# SoundChip.net
KiCad netlist of a schematic drawn in Altium Designer
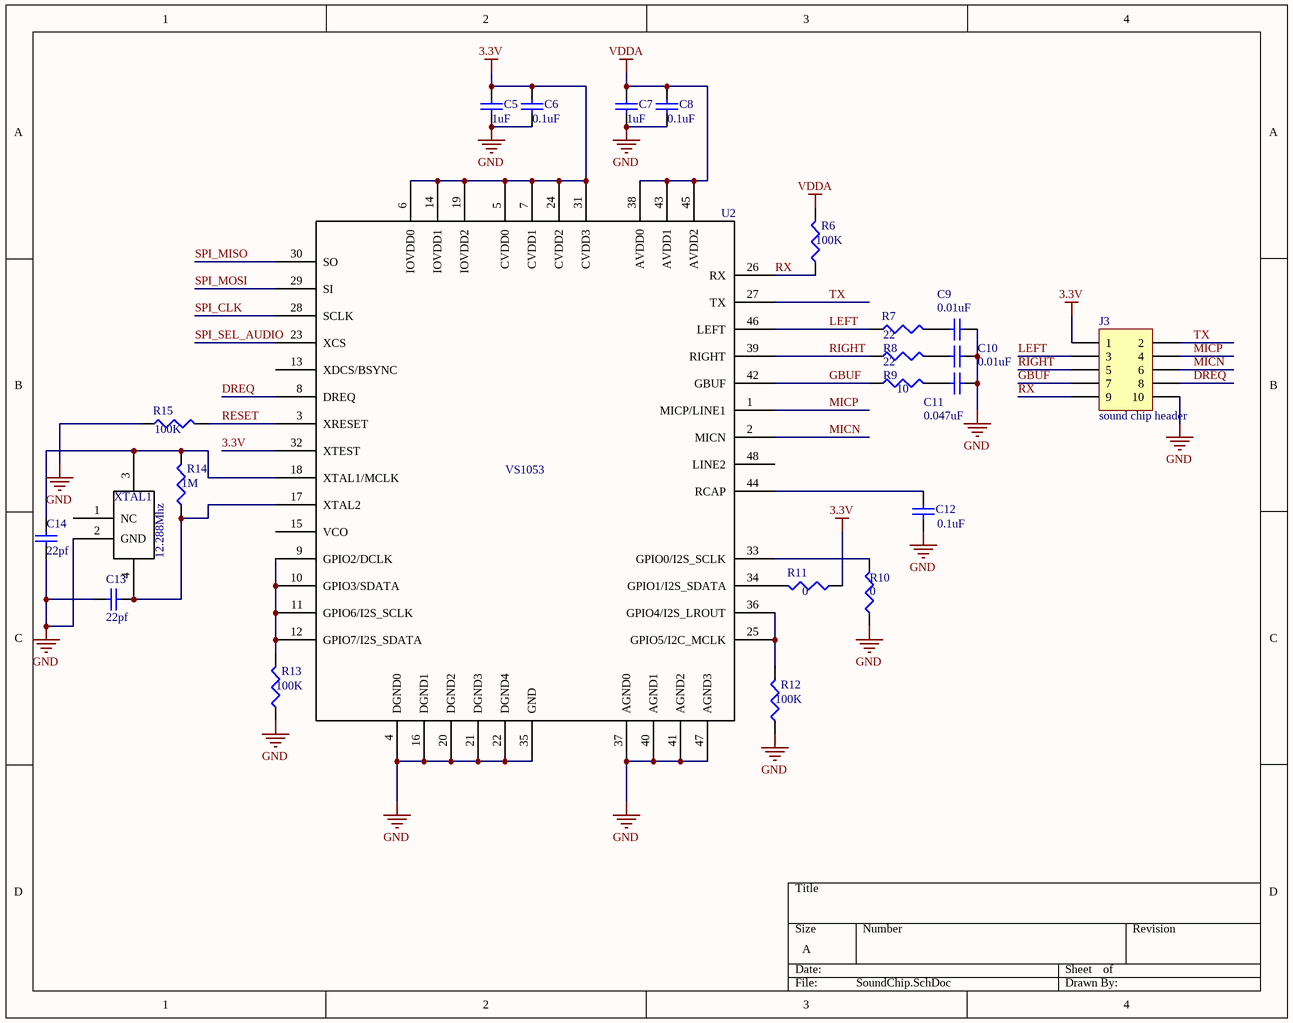
[diagram p0: SoundChip.SchDoc]

(export (version "E")
  (design (tool "Eeschema 10.0.6"))
  (components
    (comp (ref "C5")
      (value "1uF")
      (footprint "CAPC1608L")
      (description "Capacitor (Semiconductor SIM Model)")
      (fields (field (name "Comment") "Cap Semi") (field (name "PUBLISHER") "Altium Limited"))
      (libsource (lib "Miscellaneous Devices") (part "Cap Semi"))
    )
    (comp (ref "C6")
      (value "0.1uF")
      (footprint "CAPC1005L")
      (description "Capacitor (Semiconductor SIM Model)")
      (fields (field (name "Comment") "Cap Semi") (field (name "PUBLISHER") "Altium Limited"))
      (libsource (lib "Miscellaneous Devices") (part "Cap Semi"))
    )
    (comp (ref "C7")
      (value "1uF")
      (footprint "CAPC1608L")
      (description "Capacitor (Semiconductor SIM Model)")
      (fields (field (name "Comment") "Cap Semi") (field (name "PUBLISHER") "Altium Limited"))
      (libsource (lib "Miscellaneous Devices") (part "Cap Semi"))
    )
    (comp (ref "C8")
      (value "0.1uF")
      (footprint "CAPC1005L")
      (description "Capacitor (Semiconductor SIM Model)")
      (fields (field (name "Comment") "Cap Semi") (field (name "PUBLISHER") "Altium Limited"))
      (libsource (lib "Miscellaneous Devices") (part "Cap Semi"))
    )
    (comp (ref "C9")
      (value "0.01uF")
      (footprint "CAPC1005L")
      (description "Capacitor (Semiconductor SIM Model)")
      (fields (field (name "Comment") "Cap Semi") (field (name "PUBLISHER") "Altium Limited"))
      (libsource (lib "Miscellaneous Devices") (part "Cap Semi"))
    )
    (comp (ref "C10")
      (value "0.01uF")
      (footprint "CAPC1005L")
      (description "Capacitor (Semiconductor SIM Model)")
      (fields (field (name "Comment") "Cap Semi") (field (name "PUBLISHER") "Altium Limited"))
      (libsource (lib "Miscellaneous Devices") (part "Cap Semi"))
    )
    (comp (ref "C11")
      (value "0.047uF")
      (footprint "CAPC1005L")
      (description "Capacitor (Semiconductor SIM Model)")
      (fields (field (name "Comment") "Cap Semi") (field (name "PUBLISHER") "Altium Limited"))
      (libsource (lib "Miscellaneous Devices") (part "Cap Semi"))
    )
    (comp (ref "C12")
      (value "0.1uF")
      (footprint "CAPC3216L")
      (description "Capacitor (Semiconductor SIM Model)")
      (fields (field (name "Comment") "Cap Semi") (field (name "PUBLISHER") "Altium Limited"))
      (libsource (lib "Miscellaneous Devices") (part "Cap Semi"))
    )
    (comp (ref "C13")
      (value "22pf")
      (footprint "CAPC1005L")
      (description "Capacitor (Semiconductor SIM Model)")
      (fields (field (name "Comment") "Cap Semi") (field (name "PUBLISHER") "Altium Limited"))
      (libsource (lib "Miscellaneous Devices") (part "Cap Semi"))
    )
    (comp (ref "C14")
      (value "22pf")
      (footprint "CAPC1005L")
      (description "Capacitor (Semiconductor SIM Model)")
      (fields (field (name "Comment") "Cap Semi") (field (name "PUBLISHER") "Altium Limited"))
      (libsource (lib "Miscellaneous Devices") (part "Cap Semi"))
    )
    (comp (ref "J3")
      (value "sound chip header")
      (footprint "HDR2X5")
      (description "Header, 5-Pin, Dual row")
      (fields (field (name "PUBLISHER") "Altium Limited"))
      (libsource (lib "Miscellaneous Connectors") (part "Header 5X2"))
    )
    (comp (ref "R6")
      (value "100K")
      (footprint "RESC1608L")
      (description "Resistor")
      (fields (field (name "Comment") "Res3") (field (name "PUBLISHER") "Altium Limited"))
      (libsource (lib "Miscellaneous Devices") (part "Res3"))
    )
    (comp (ref "R7")
      (value "22")
      (footprint "RESC1608L")
      (description "Resistor")
      (fields (field (name "Comment") "Res3") (field (name "PUBLISHER") "Altium Limited"))
      (libsource (lib "Miscellaneous Devices") (part "Res3"))
    )
    (comp (ref "R8")
      (value "22")
      (footprint "RESC1608L")
      (description "Resistor")
      (fields (field (name "Comment") "Res3") (field (name "PUBLISHER") "Altium Limited"))
      (libsource (lib "Miscellaneous Devices") (part "Res3"))
    )
    (comp (ref "R9")
      (value "10")
      (footprint "RESC1608L")
      (description "Resistor")
      (fields (field (name "Comment") "Res3") (field (name "PUBLISHER") "Altium Limited"))
      (libsource (lib "Miscellaneous Devices") (part "Res3"))
    )
    (comp (ref "R10")
      (value "0")
      (footprint "RESC1608L")
      (description "Resistor")
      (fields (field (name "Comment") "Res3") (field (name "PUBLISHER") "Altium Limited"))
      (libsource (lib "Miscellaneous Devices") (part "Res3"))
    )
    (comp (ref "R11")
      (value "0")
      (footprint "RESC1608L")
      (description "Resistor")
      (fields (field (name "Comment") "Res3") (field (name "PUBLISHER") "Altium Limited"))
      (libsource (lib "Miscellaneous Devices") (part "Res3"))
    )
    (comp (ref "R12")
      (value "100K")
      (footprint "RESC1608L")
      (description "Resistor")
      (fields (field (name "Comment") "Res3") (field (name "PUBLISHER") "Altium Limited"))
      (libsource (lib "Miscellaneous Devices") (part "Res3"))
    )
    (comp (ref "R13")
      (value "100K")
      (footprint "RESC1608L")
      (description "Resistor")
      (fields (field (name "Comment") "Res3") (field (name "PUBLISHER") "Altium Limited"))
      (libsource (lib "Miscellaneous Devices") (part "Res3"))
    )
    (comp (ref "R14")
      (value "1M")
      (footprint "RESC1608L")
      (description "Resistor")
      (fields (field (name "Comment") "Res3") (field (name "PUBLISHER") "Altium Limited"))
      (libsource (lib "Miscellaneous Devices") (part "Res3"))
    )
    (comp (ref "R15")
      (value "100K")
      (footprint "RESC1608L")
      (description "Resistor")
      (fields (field (name "Comment") "Res3") (field (name "PUBLISHER") "Altium Limited"))
      (libsource (lib "Miscellaneous Devices") (part "Res3"))
    )
    (comp (ref "U2") (value "VS1053") (footprint "LQFP-48") (libsource (lib "mrone") (part "VS1053")))
    (comp (ref "XTAL1")
      (value "12.288Mhz")
      (footprint "Crystal")
      (description "FOX924B crystal")
      (libsource (lib "mrone") (part "SoundCrystal"))
    )
  )
  (nets
    (net (code "1") (name "/DREQ") (class "Default")
      (node (ref "J3") (pin "8") (pinfunction "8_8") (pintype "passive"))
      (node (ref "U2") (pin "8") (pinfunction "DREQ_8") (pintype "passive"))
    )
    (net (code "2") (name "/GBUF") (class "Default")
      (node (ref "J3") (pin "7") (pinfunction "7_7") (pintype "passive"))
      (node (ref "R9") (pin "1") (pinfunction "1_1") (pintype "passive"))
      (node (ref "U2") (pin "42") (pinfunction "GBUF_42") (pintype "passive"))
    )
    (net (code "3") (name "/LEFT") (class "Default")
      (node (ref "J3") (pin "3") (pinfunction "3_3") (pintype "passive"))
      (node (ref "R7") (pin "1") (pinfunction "1_1") (pintype "passive"))
      (node (ref "U2") (pin "46") (pinfunction "LEFT_46") (pintype "passive"))
    )
    (net (code "4") (name "/MICN") (class "Default")
      (node (ref "J3") (pin "6") (pinfunction "6_6") (pintype "passive"))
      (node (ref "U2") (pin "2") (pinfunction "MICN_2") (pintype "passive"))
    )
    (net (code "5") (name "/MICP") (class "Default")
      (node (ref "J3") (pin "4") (pinfunction "4_4") (pintype "passive"))
      (node (ref "U2") (pin "1") (pinfunction "MICP/LINE1_1") (pintype "passive"))
    )
    (net (code "6") (name "/RESET") (class "Default")
      (node (ref "R15") (pin "2") (pinfunction "2_2") (pintype "passive"))
      (node (ref "U2") (pin "3") (pinfunction "XRESET_3") (pintype "passive"))
    )
    (net (code "7") (name "/RIGHT") (class "Default")
      (node (ref "J3") (pin "5") (pinfunction "5_5") (pintype "passive"))
      (node (ref "R8") (pin "1") (pinfunction "1_1") (pintype "passive"))
      (node (ref "U2") (pin "39") (pinfunction "RIGHT_39") (pintype "passive"))
    )
    (net (code "8") (name "/RX") (class "Default")
      (node (ref "J3") (pin "9") (pinfunction "9_9") (pintype "passive"))
      (node (ref "R6") (pin "1") (pinfunction "1_1") (pintype "passive"))
      (node (ref "U2") (pin "26") (pinfunction "RX_26") (pintype "passive"))
    )
    (net (code "9") (name "/SPI_CLK") (class "Default")
      (node (ref "U2") (pin "28") (pinfunction "SCLK_28") (pintype "passive"))
    )
    (net (code "10") (name "/SPI_MISO") (class "Default")
      (node (ref "U2") (pin "30") (pinfunction "SO_30") (pintype "passive"))
    )
    (net (code "11") (name "/SPI_MOSI") (class "Default")
      (node (ref "U2") (pin "29") (pinfunction "SI_29") (pintype "passive"))
    )
    (net (code "12") (name "/SPI_SEL_AUDIO") (class "Default")
      (node (ref "U2") (pin "23") (pinfunction "XCS_23") (pintype "passive"))
    )
    (net (code "13") (name "/TX") (class "Default")
      (node (ref "J3") (pin "2") (pinfunction "2_2") (pintype "passive"))
      (node (ref "U2") (pin "27") (pinfunction "TX_27") (pintype "passive"))
    )
    (net (code "14") (name "3.3V") (class "Default")
      (node (ref "C5") (pin "1") (pinfunction "1_1") (pintype "passive"))
      (node (ref "C6") (pin "2") (pinfunction "2_2") (pintype "passive"))
      (node (ref "J3") (pin "1") (pinfunction "1_1") (pintype "passive"))
      (node (ref "R11") (pin "1") (pinfunction "1_1") (pintype "passive"))
      (node (ref "U2") (pin "14") (pinfunction "IOVDD1_14") (pintype "passive"))
      (node (ref "U2") (pin "19") (pinfunction "IOVDD2_19") (pintype "passive"))
      (node (ref "U2") (pin "24") (pinfunction "CVDD2_24") (pintype "passive"))
      (node (ref "U2") (pin "31") (pinfunction "CVDD3_31") (pintype "passive"))
      (node (ref "U2") (pin "32") (pinfunction "XTEST_32") (pintype "passive"))
      (node (ref "U2") (pin "5") (pinfunction "CVDD0_5") (pintype "passive"))
      (node (ref "U2") (pin "6") (pinfunction "IOVDD0_6") (pintype "passive"))
      (node (ref "U2") (pin "7") (pinfunction "CVDD1_7") (pintype "passive"))
    )
    (net (code "15") (name "GND") (class "Default")
      (node (ref "C10") (pin "2") (pinfunction "2_2") (pintype "passive"))
      (node (ref "C11") (pin "2") (pinfunction "2_2") (pintype "passive"))
      (node (ref "C12") (pin "1") (pinfunction "1_1") (pintype "passive"))
      (node (ref "C13") (pin "2") (pinfunction "2_2") (pintype "passive"))
      (node (ref "C14") (pin "1") (pinfunction "1_1") (pintype "passive"))
      (node (ref "C5") (pin "2") (pinfunction "2_2") (pintype "passive"))
      (node (ref "C6") (pin "1") (pinfunction "1_1") (pintype "passive"))
      (node (ref "C7") (pin "2") (pinfunction "2_2") (pintype "passive"))
      (node (ref "C8") (pin "1") (pinfunction "1_1") (pintype "passive"))
      (node (ref "C9") (pin "2") (pinfunction "2_2") (pintype "passive"))
      (node (ref "J3") (pin "10") (pinfunction "10_10") (pintype "passive"))
      (node (ref "R10") (pin "1") (pinfunction "1_1") (pintype "passive"))
      (node (ref "R12") (pin "1") (pinfunction "1_1") (pintype "passive"))
      (node (ref "R13") (pin "1") (pinfunction "1_1") (pintype "passive"))
      (node (ref "R15") (pin "1") (pinfunction "1_1") (pintype "passive"))
      (node (ref "U2") (pin "16") (pinfunction "DGND1_16") (pintype "passive"))
      (node (ref "U2") (pin "20") (pinfunction "DGND2_20") (pintype "passive"))
      (node (ref "U2") (pin "21") (pinfunction "DGND3_21") (pintype "passive"))
      (node (ref "U2") (pin "22") (pinfunction "DGND4_22") (pintype "passive"))
      (node (ref "U2") (pin "35") (pinfunction "GND_35") (pintype "passive"))
      (node (ref "U2") (pin "37") (pinfunction "AGND0_37") (pintype "passive"))
      (node (ref "U2") (pin "4") (pinfunction "DGND0_4") (pintype "passive"))
      (node (ref "U2") (pin "40") (pinfunction "AGND1_40") (pintype "passive"))
      (node (ref "U2") (pin "41") (pinfunction "AGND2_41") (pintype "passive"))
      (node (ref "U2") (pin "47") (pinfunction "AGND3_47") (pintype "passive"))
      (node (ref "XTAL1") (pin "2") (pinfunction "GND_2") (pintype "passive"))
    )
    (net (code "16") (name "Net-(C9-Pad1)") (class "Default")
      (node (ref "C9") (pin "1") (pinfunction "1_1") (pintype "passive"))
      (node (ref "R7") (pin "2") (pinfunction "2_2") (pintype "passive"))
    )
    (net (code "17") (name "Net-(C10-Pad1)") (class "Default")
      (node (ref "C10") (pin "1") (pinfunction "1_1") (pintype "passive"))
      (node (ref "R8") (pin "2") (pinfunction "2_2") (pintype "passive"))
    )
    (net (code "18") (name "Net-(C11-Pad1)") (class "Default")
      (node (ref "C11") (pin "1") (pinfunction "1_1") (pintype "passive"))
      (node (ref "R9") (pin "2") (pinfunction "2_2") (pintype "passive"))
    )
    (net (code "19") (name "Net-(U2-GPIO0{slash}I2S_SCLK)") (class "Default")
      (node (ref "R10") (pin "2") (pinfunction "2_2") (pintype "passive"))
      (node (ref "U2") (pin "33") (pinfunction "GPIO0/I2S_SCLK_33") (pintype "passive"))
    )
    (net (code "20") (name "Net-(U2-GPIO1{slash}I2S_SDATA)") (class "Default")
      (node (ref "R11") (pin "2") (pinfunction "2_2") (pintype "passive"))
      (node (ref "U2") (pin "34") (pinfunction "GPIO1/I2S_SDATA_34") (pintype "passive"))
    )
    (net (code "21") (name "Net-(U2-GPIO2{slash}DCLK)") (class "Default")
      (node (ref "R13") (pin "2") (pinfunction "2_2") (pintype "passive"))
      (node (ref "U2") (pin "10") (pinfunction "GPIO3/SDATA_10") (pintype "passive"))
      (node (ref "U2") (pin "11") (pinfunction "GPIO6/I2S_SCLK_11") (pintype "passive"))
      (node (ref "U2") (pin "12") (pinfunction "GPIO7/I2S_SDATA_12") (pintype "passive"))
      (node (ref "U2") (pin "9") (pinfunction "GPIO2/DCLK_9") (pintype "passive"))
    )
    (net (code "22") (name "Net-(U2-GPIO4{slash}I2S_LROUT)") (class "Default")
      (node (ref "R12") (pin "2") (pinfunction "2_2") (pintype "passive"))
      (node (ref "U2") (pin "25") (pinfunction "GPIO5/I2C_MCLK_25") (pintype "passive"))
      (node (ref "U2") (pin "36") (pinfunction "GPIO4/I2S_LROUT_36") (pintype "passive"))
    )
    (net (code "23") (name "Net-(U2-RCAP)") (class "Default")
      (node (ref "C12") (pin "2") (pinfunction "2_2") (pintype "passive"))
      (node (ref "U2") (pin "44") (pinfunction "RCAP_44") (pintype "passive"))
    )
    (net (code "24") (name "Net-(U2-XTAL1{slash}MCLK)") (class "Default")
      (node (ref "C14") (pin "2") (pinfunction "2_2") (pintype "passive"))
      (node (ref "R14") (pin "2") (pinfunction "2_2") (pintype "passive"))
      (node (ref "U2") (pin "18") (pinfunction "XTAL1/MCLK_18") (pintype "passive"))
      (node (ref "XTAL1") (pin "3") (pintype "passive"))
    )
    (net (code "25") (name "Net-(U2-XTAL2)") (class "Default")
      (node (ref "C13") (pin "1") (pinfunction "1_1") (pintype "passive"))
      (node (ref "R14") (pin "1") (pinfunction "1_1") (pintype "passive"))
      (node (ref "U2") (pin "17") (pinfunction "XTAL2_17") (pintype "passive"))
      (node (ref "XTAL1") (pin "4") (pinfunction "4_4") (pintype "passive"))
    )
    (net (code "26") (name "VDDA") (class "Default")
      (node (ref "C7") (pin "1") (pinfunction "1_1") (pintype "passive"))
      (node (ref "C8") (pin "2") (pinfunction "2_2") (pintype "passive"))
      (node (ref "R6") (pin "2") (pinfunction "2_2") (pintype "passive"))
      (node (ref "U2") (pin "38") (pinfunction "AVDD0_38") (pintype "passive"))
      (node (ref "U2") (pin "43") (pinfunction "AVDD1_43") (pintype "passive"))
      (node (ref "U2") (pin "45") (pinfunction "AVDD2_45") (pintype "passive"))
    )
    (net (code "27") (name "unconnected-(U2-LINE2-Pad48)") (class "Default")
      (node (ref "U2") (pin "48") (pinfunction "LINE2_48") (pintype "passive"))
    )
    (net (code "28") (name "unconnected-(U2-VCO-Pad15)") (class "Default")
      (node (ref "U2") (pin "15") (pinfunction "VCO_15") (pintype "passive"))
    )
    (net (code "29") (name "unconnected-(U2-XDCS{slash}BSYNC-Pad13)") (class "Default")
      (node (ref "U2") (pin "13") (pinfunction "XDCS/BSYNC_13") (pintype "passive"))
    )
    (net (code "30") (name "unconnected-(XTAL1-NC-Pad1)") (class "Default")
      (node (ref "XTAL1") (pin "1") (pinfunction "NC_1") (pintype "passive"))
    )
  )
)
